# robot-joystick.net
KiCad netlist of a schematic drawn in EAGLE
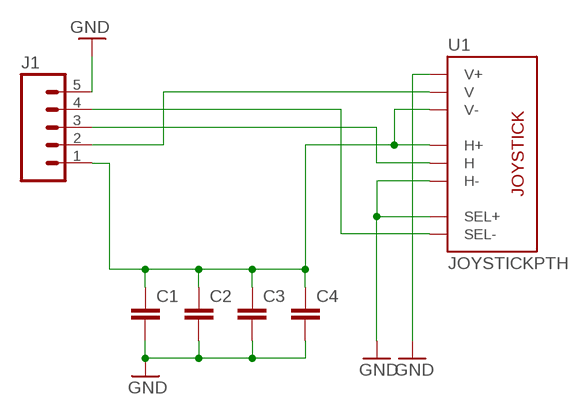
[diagram p0: schematic, sheet 1]

(export (version "E")
  (design (tool "Eeschema 10.0.6"))
  (components
    (comp (ref "C1")
      (value "C-EUC3216")
      (footprint "eagle-import:C3216")
      (libsource (lib "eagle-import") (part "C-EUC3216"))
    )
    (comp (ref "C2")
      (value "C-EUC3216")
      (footprint "eagle-import:C3216")
      (libsource (lib "eagle-import") (part "C-EUC3216"))
    )
    (comp (ref "C3")
      (value "C-EUC3216")
      (footprint "eagle-import:C3216")
      (libsource (lib "eagle-import") (part "C-EUC3216"))
    )
    (comp (ref "C4")
      (value "C-EUC3216")
      (footprint "eagle-import:C3216")
      (libsource (lib "eagle-import") (part "C-EUC3216"))
    )
    (comp (ref "J1")
      (value "M05PTH")
      (footprint "eagle-import:1X05")
      (libsource (lib "eagle-import") (part "M05PTH"))
    )
    (comp (ref "U1")
      (value "JOYSTICKPTH")
      (footprint "eagle-import:JOYSTICK")
      (libsource (lib "eagle-import") (part "JOYSTICKPTH"))
    )
  )
  (nets
    (net (code "1") (name "GND") (class "Default")
      (node (ref "C1") (pin "2") (pinfunction "2_2") (pintype "passive"))
      (node (ref "C2") (pin "2") (pinfunction "2_2") (pintype "passive"))
      (node (ref "C3") (pin "2") (pinfunction "2_2") (pintype "passive"))
      (node (ref "C4") (pin "2") (pinfunction "2_2") (pintype "passive"))
      (node (ref "J1") (pin "5") (pinfunction "5_5") (pintype "passive"))
      (node (ref "U1") (pin "B1A") (pinfunction "SEL+_B1A") (pintype "bidirectional"))
      (node (ref "U1") (pin "H3") (pinfunction "H-_H3") (pintype "bidirectional"))
      (node (ref "U1") (pin "V1") (pinfunction "V+_V1") (pintype "bidirectional"))
    )
    (net (code "2") (name "Net-(U1-H)") (class "Default")
      (node (ref "J1") (pin "3") (pinfunction "3_3") (pintype "passive"))
      (node (ref "U1") (pin "H2") (pinfunction "H_H2") (pintype "bidirectional"))
    )
    (net (code "3") (name "Net-(U1-H+)") (class "Default")
      (node (ref "C1") (pin "1") (pinfunction "1_1") (pintype "passive"))
      (node (ref "C2") (pin "1") (pinfunction "1_1") (pintype "passive"))
      (node (ref "C3") (pin "1") (pinfunction "1_1") (pintype "passive"))
      (node (ref "C4") (pin "1") (pinfunction "1_1") (pintype "passive"))
      (node (ref "J1") (pin "1") (pinfunction "1_1") (pintype "passive"))
      (node (ref "U1") (pin "H1") (pinfunction "H+_H1") (pintype "bidirectional"))
      (node (ref "U1") (pin "V3") (pinfunction "V-_V3") (pintype "bidirectional"))
    )
    (net (code "4") (name "Net-(U1-SEL-)") (class "Default")
      (node (ref "J1") (pin "4") (pinfunction "4_4") (pintype "passive"))
      (node (ref "U1") (pin "B2A") (pinfunction "SEL-_B2A") (pintype "bidirectional"))
    )
    (net (code "5") (name "Net-(U1-V)") (class "Default")
      (node (ref "J1") (pin "2") (pinfunction "2_2") (pintype "passive"))
      (node (ref "U1") (pin "V2") (pinfunction "V_V2") (pintype "bidirectional"))
    )
  )
)
